# KUBODriver_DC.net
KiCad netlist of a schematic drawn in Altium Designer
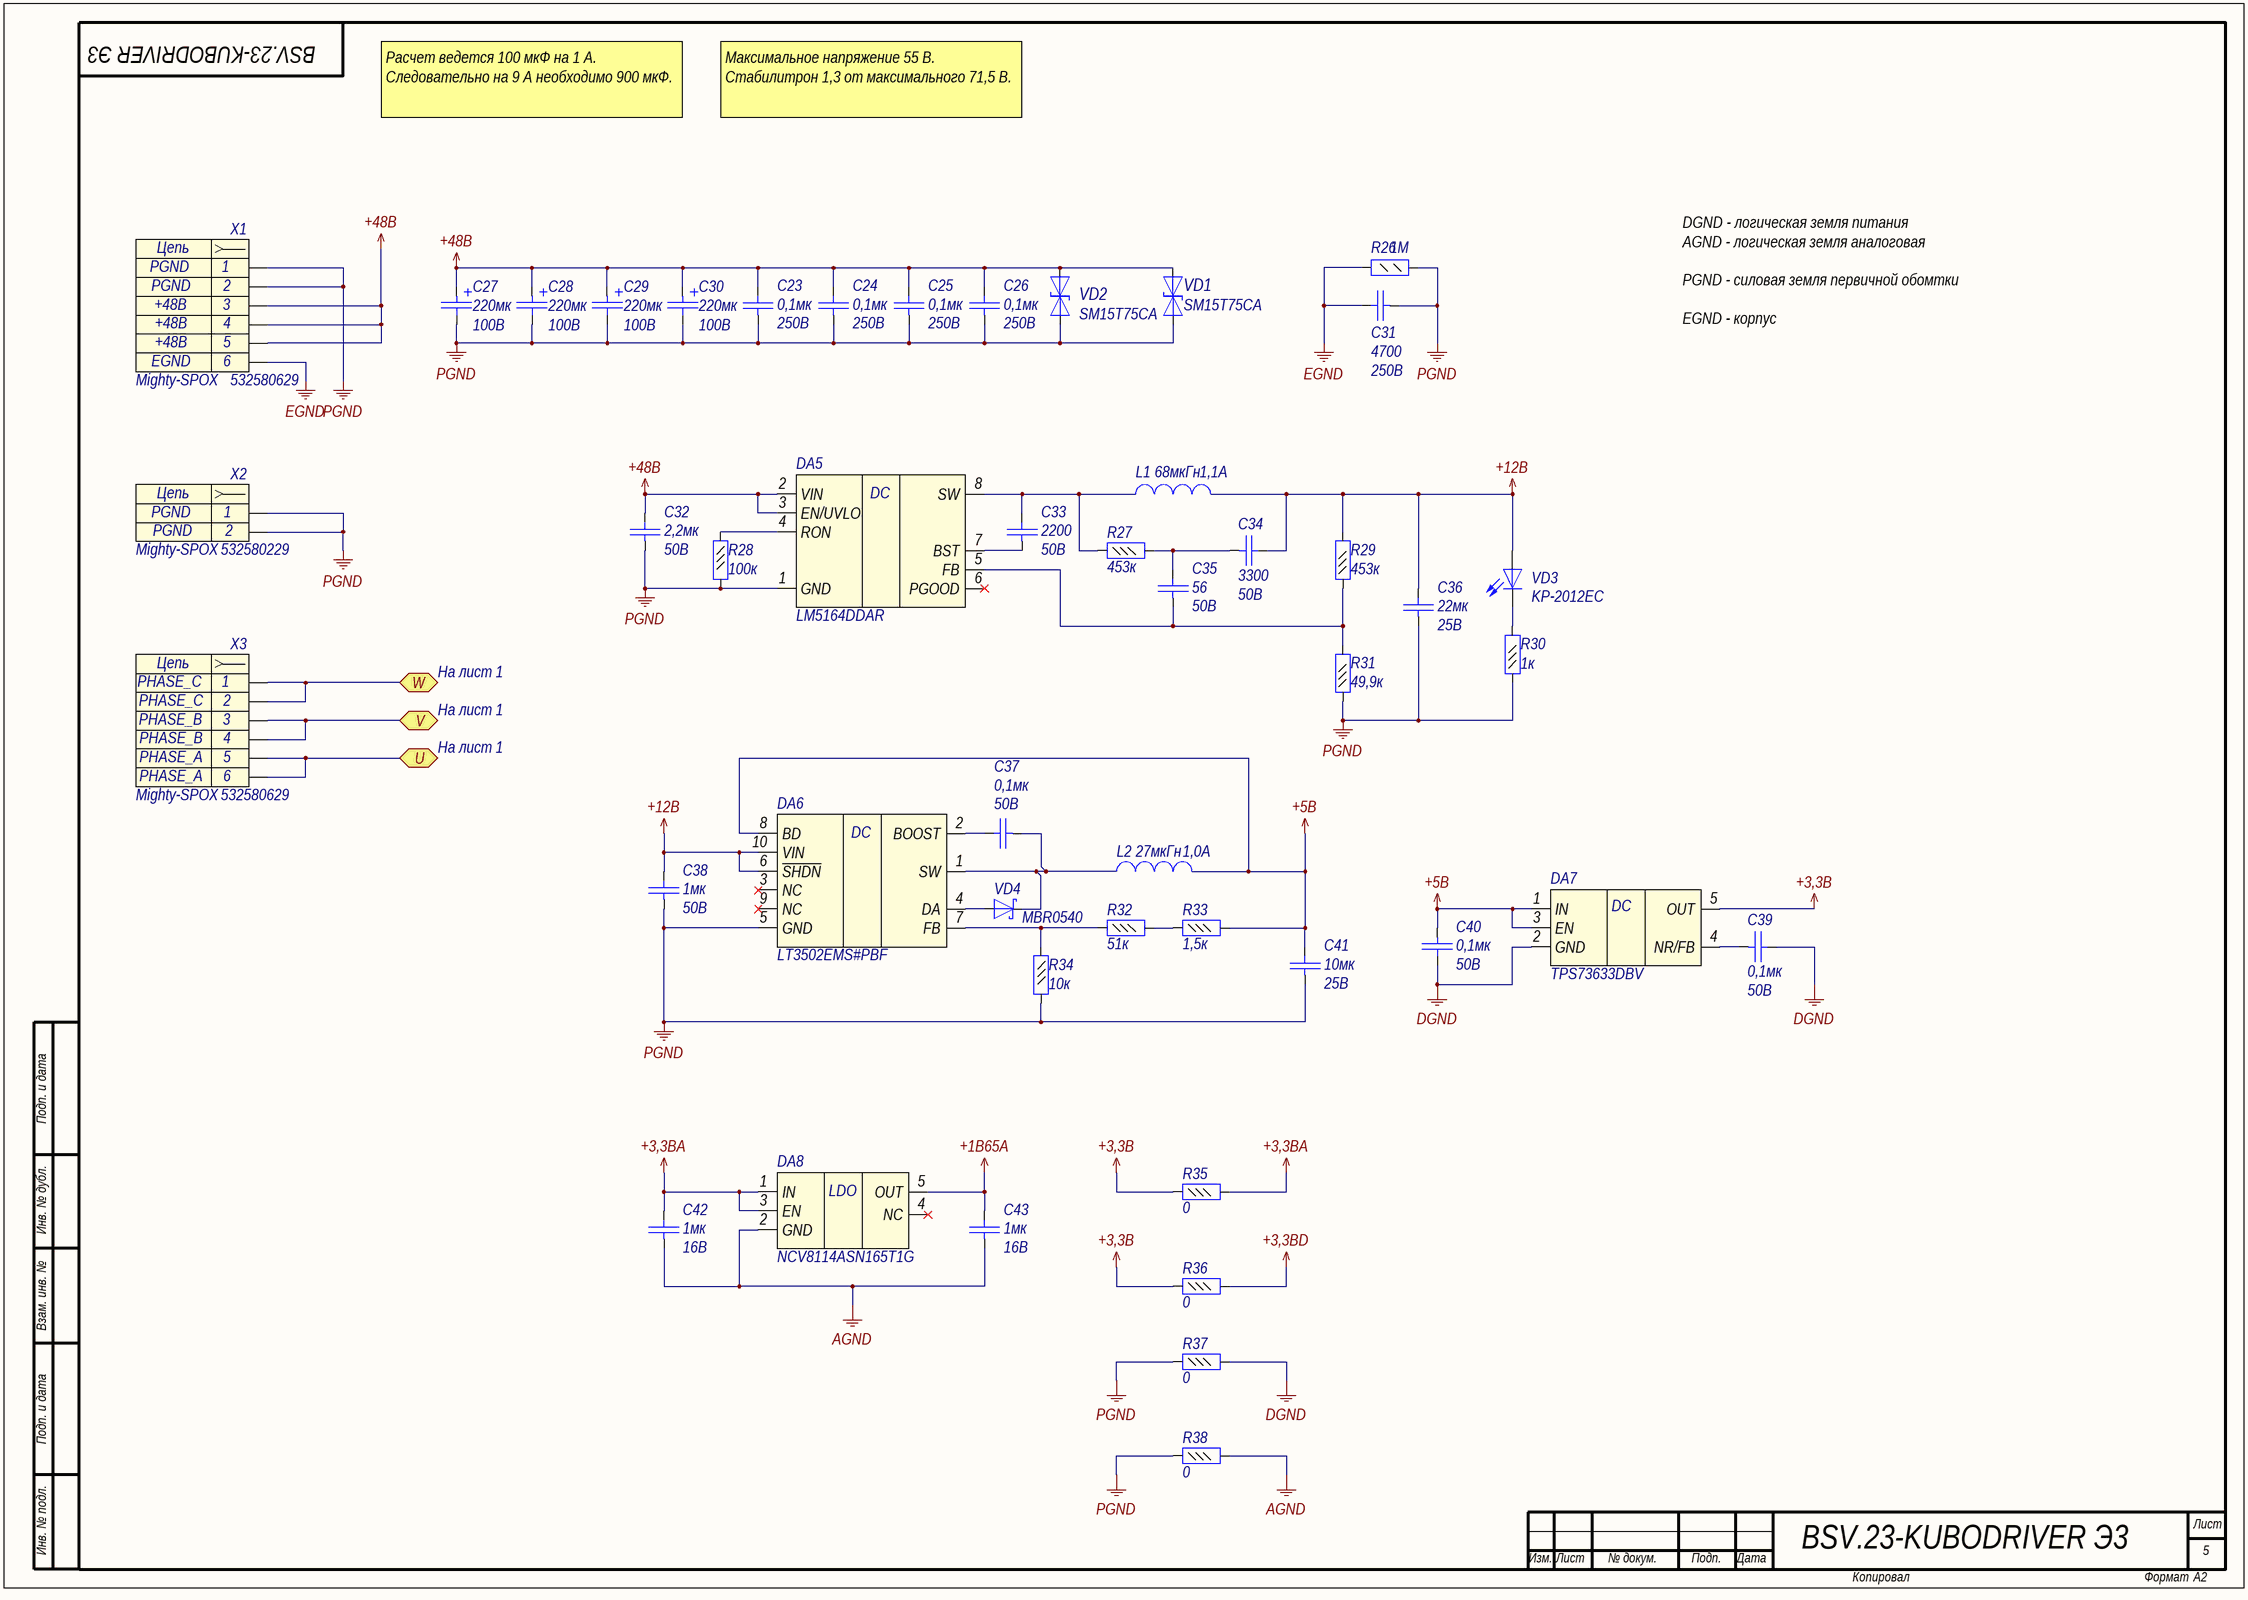
[diagram p0: KUBODriver_DC.SchDoc]

(export (version "E")
  (design (tool "Eeschema 10.0.6"))
  (components
    (comp (ref "C23")
      (value "0,1мк")
      (footprint "C1206")
      (description "Конденсатор")
      (fields
        (field (name "VOLTAGE") "250В")
        (field (name "PART NUMBER") "GRM31CR72E104K")
        (field (name "Comment") "Capacitor")
      )
      (libsource (lib "MOP44") (part "Capacitor"))
    )
    (comp (ref "C24")
      (value "0,1мк")
      (footprint "C1206")
      (description "Конденсатор")
      (fields
        (field (name "VOLTAGE") "250В")
        (field (name "PART NUMBER") "GRM31CR72E104K")
        (field (name "Comment") "Capacitor")
      )
      (libsource (lib "MOP44") (part "Capacitor"))
    )
    (comp (ref "C25")
      (value "0,1мк")
      (footprint "C1206")
      (description "Конденсатор")
      (fields
        (field (name "VOLTAGE") "250В")
        (field (name "PART NUMBER") "GRM31CR72E104K")
        (field (name "Comment") "Capacitor")
      )
      (libsource (lib "MOP44") (part "Capacitor"))
    )
    (comp (ref "C26")
      (value "0,1мк")
      (footprint "C1206")
      (description "Конденсатор")
      (fields
        (field (name "VOLTAGE") "250В")
        (field (name "PART NUMBER") "GRM31CR72E104K")
        (field (name "Comment") "Capacitor")
      )
      (libsource (lib "MOP44") (part "Capacitor"))
    )
    (comp (ref "C27")
      (value "220мк")
      (footprint "K50-35(12.5X25)_V")
      (description "Конденсатор полярный")
      (fields
        (field (name "VOLTAGE") "100B")
        (field (name "PART NUMBER") "B41851A9227M000")
        (field (name "Comment") "Capacitor_pol")
      )
      (libsource (lib "MOP44") (part "Capacitor_pol"))
    )
    (comp (ref "C28")
      (value "220мк")
      (footprint "K50-35(12.5X25)_V")
      (description "Конденсатор полярный")
      (fields
        (field (name "VOLTAGE") "100B")
        (field (name "PART NUMBER") "B41851A9227M000")
        (field (name "Comment") "Capacitor_pol")
      )
      (libsource (lib "MOP44") (part "Capacitor_pol"))
    )
    (comp (ref "C29")
      (value "220мк")
      (footprint "K50-35(12.5X25)_V")
      (description "Конденсатор полярный")
      (fields
        (field (name "VOLTAGE") "100B")
        (field (name "PART NUMBER") "B41851A9227M000")
        (field (name "Comment") "Capacitor_pol")
      )
      (libsource (lib "MOP44") (part "Capacitor_pol"))
    )
    (comp (ref "C30")
      (value "220мк")
      (footprint "K50-35(12.5X25)_V")
      (description "Конденсатор полярный")
      (fields
        (field (name "VOLTAGE") "100B")
        (field (name "PART NUMBER") "B41851A9227M000")
        (field (name "Comment") "Capacitor_pol")
      )
      (libsource (lib "MOP44") (part "Capacitor_pol"))
    )
    (comp (ref "C31")
      (value "4700")
      (footprint "C0805")
      (description "Конденсатор")
      (fields
        (field (name "VOLTAGE") "250В")
        (field (name "PART NUMBER") "GRM21AR72E472KW")
        (field (name "Comment") "Capacitor")
      )
      (libsource (lib "MOP44") (part "Capacitor"))
    )
    (comp (ref "C32")
      (value "2,2мк")
      (footprint "C0603")
      (description "Конденсатор")
      (fields
        (field (name "VOLTAGE") "50B")
        (field (name "PART NUMBER") "GRM188R71A225KE15D")
        (field (name "Comment") "Capacitor")
      )
      (libsource (lib "MOP44") (part "Capacitor"))
    )
    (comp (ref "C33")
      (value "2200")
      (footprint "C0402")
      (description "Конденсатор")
      (fields
        (field (name "VOLTAGE") "50B")
        (field (name "PART NUMBER") "GRM155R71H222K")
        (field (name "Comment") "Capacitor")
      )
      (libsource (lib "MOP44") (part "Capacitor"))
    )
    (comp (ref "C34")
      (value "3300")
      (footprint "C0402")
      (description "Конденсатор")
      (fields
        (field (name "VOLTAGE") "50В")
        (field (name "PART NUMBER") "GRM155R71H332KA01D ")
        (field (name "Comment") "Capacitor")
      )
      (libsource (lib "MOP44") (part "Capacitor"))
    )
    (comp (ref "C35")
      (value "56")
      (footprint "C0402")
      (description "Конденсатор")
      (fields
        (field (name "VOLTAGE") "50B")
        (field (name "PART NUMBER") "GRM1555C1H560J*")
        (field (name "Comment") "Capacitor")
      )
      (libsource (lib "MOP44") (part "Capacitor"))
    )
    (comp (ref "C36")
      (value "22мк")
      (footprint "C1210")
      (description "Конденсатор")
      (fields
        (field (name "VOLTAGE") "25B")
        (field (name "PART NUMBER") "TMK325B7226KMHT")
        (field (name "Comment") "Capacitor")
      )
      (libsource (lib "MOP44") (part "Capacitor"))
    )
    (comp (ref "C37")
      (value "0,1мк")
      (footprint "C0402")
      (description "Конденсатор")
      (fields
        (field (name "VOLTAGE") "50В")
        (field (name "PART NUMBER") "GRM155R71H104KE14D ")
        (field (name "Comment") "Capacitor")
      )
      (libsource (lib "MOP44") (part "Capacitor"))
    )
    (comp (ref "C38")
      (value "1мк")
      (footprint "C0805")
      (description "Конденсатор")
      (fields
        (field (name "VOLTAGE") "50B")
        (field (name "PART NUMBER") "GRM21BR71H105K")
        (field (name "Comment") "Capacitor")
      )
      (libsource (lib "MOP44") (part "Capacitor"))
    )
    (comp (ref "C39")
      (value "0,1мк")
      (footprint "C0402")
      (description "Конденсатор")
      (fields
        (field (name "VOLTAGE") "50В")
        (field (name "PART NUMBER") "GRM155R71H104KE14D ")
        (field (name "Comment") "Capacitor")
      )
      (libsource (lib "MOP44") (part "Capacitor"))
    )
    (comp (ref "C40")
      (value "0,1мк")
      (footprint "C0402")
      (description "Конденсатор")
      (fields
        (field (name "VOLTAGE") "50В")
        (field (name "PART NUMBER") "GRM155R71H104KE14D ")
        (field (name "Comment") "Capacitor")
      )
      (libsource (lib "MOP44") (part "Capacitor"))
    )
    (comp (ref "C41")
      (value "10мк")
      (footprint "C1206")
      (description "Конденсатор")
      (fields
        (field (name "VOLTAGE") "25В")
        (field (name "PART NUMBER") "GRM31CR71E106KA12L*")
        (field (name "Comment") "Capacitor")
      )
      (libsource (lib "MOP44") (part "Capacitor"))
    )
    (comp (ref "C42")
      (value "1мк")
      (footprint "C0603")
      (description "Конденсатор")
      (fields
        (field (name "VOLTAGE") "16B")
        (field (name "PART NUMBER") "GRM188R71C105KA12D**")
        (field (name "Comment") "Capacitor")
      )
      (libsource (lib "MOP44") (part "Capacitor"))
    )
    (comp (ref "C43")
      (value "1мк")
      (footprint "C0603")
      (description "Конденсатор")
      (fields
        (field (name "VOLTAGE") "16B")
        (field (name "PART NUMBER") "GRM188R71C105KA12D**")
        (field (name "Comment") "Capacitor")
      )
      (libsource (lib "MOP44") (part "Capacitor"))
    )
    (comp (ref "DA5")
      (value "LM5164")
      (footprint "SO Powerpad8")
      (description "1-A synchronous buck DC/DC converter with ultra-low IQ")
      (fields (field (name "PART NUMBER") "LM5164DDAR") (field (name "MANUFACTURER") "Texas Instruments"))
      (libsource (lib "MOP44") (part "LM5164"))
    )
    (comp (ref "DA6")
      (value "LT3502_MS")
      (footprint "MSOP10")
      (description "1.1MHz/2.2MHz, 500mA  Step-Down Regulators")
      (fields (field (name "PART NUMBER") "LT3502EMS#PBF") (field (name "MANUFACTURER") "Linear Technology"))
      (libsource (lib "MOP44") (part "LT3502_MS"))
    )
    (comp (ref "DA7")
      (value "TPS736DBV")
      (footprint "SOT23-5")
      (description "400-mA Low-Dropout Regulator with Reverse Current  Protection")
      (fields (field (name "PART NUMBER") "TPS73633DBV") (field (name "MANUFACTURER") "Texas Instruments"))
      (libsource (lib "MOP44") (part "TPS736DBV"))
    )
    (comp (ref "DA8")
      (value "NCV8114")
      (footprint "TSOP5")
      (description "300 mA CMOS Low Dropout  Regulator")
      (fields
        (field (name "PART NUMBER") "NCV8114ASN165T1G")
        (field (name "MANUFACTURER") "ON Semiconductor")
      )
      (libsource (lib "MOP44") (part "NCV8114"))
    )
    (comp (ref "L1")
      (value "68мкГн")
      (footprint "SDR1006")
      (description "EMI Suppression Filter")
      (fields
        (field (name "RATED CURRENT") "1,1A")
        (field (name "PART NUMBER") "SDR1006- 680KL")
        (field (name "Comment") "Inductor")
      )
      (libsource (lib "MOP44") (part "Inductor"))
    )
    (comp (ref "L2")
      (value "27мкГн")
      (footprint "SDR0604")
      (description "EMI Suppression Filter")
      (fields
        (field (name "RATED CURRENT") "1,0A")
        (field (name "PART NUMBER") "SDR0604- 270YL")
        (field (name "Comment") "Inductor")
      )
      (libsource (lib "MOP44") (part "Inductor"))
    )
    (comp (ref "R26")
      (value "1М")
      (footprint "R0805")
      (description "Резистор")
      (fields (field (name "PART NUMBER") "RC0805FR-071ML") (field (name "POWER") "0,125Вт"))
      (libsource (lib "MOP44") (part "Resistor_0,125Вт"))
    )
    (comp (ref "R27")
      (value "453к")
      (footprint "R0402")
      (description "Резистор")
      (fields (field (name "PART NUMBER") "RC0402FR-07453KL") (field (name "POWER") "0,062Вт"))
      (libsource (lib "MOP44") (part "Resistor_0,062Вт"))
    )
    (comp (ref "R28")
      (value "100к")
      (footprint "R0402")
      (description "Резистор")
      (fields (field (name "PART NUMBER") "RC0402FR-07100KL") (field (name "POWER") "0,062Вт"))
      (libsource (lib "") (part "Resistor_0,062Вт_1"))
    )
    (comp (ref "R29")
      (value "453к")
      (footprint "R0402")
      (description "Резистор")
      (fields (field (name "PART NUMBER") "RC0402FR-07453KL") (field (name "POWER") "0,062Вт"))
      (libsource (lib "") (part "Resistor_0,062Вт_2"))
    )
    (comp (ref "R30")
      (value "1к")
      (footprint "R0402")
      (description "Резистор")
      (fields (field (name "PART NUMBER") "RC0402FR-071KL") (field (name "POWER") "0,062Вт"))
      (libsource (lib "") (part "Resistor_0,062Вт_2"))
    )
    (comp (ref "R31")
      (value "49,9к")
      (footprint "R0402")
      (description "Резистор")
      (fields (field (name "PART NUMBER") "RC0402FR-0749K9L") (field (name "POWER") "0,062Вт"))
      (libsource (lib "") (part "Resistor_0,062Вт_2"))
    )
    (comp (ref "R32")
      (value "51к")
      (footprint "R0402")
      (description "Резистор")
      (fields (field (name "PART NUMBER") "RC0402FR-0751KL") (field (name "POWER") "0,062Вт"))
      (libsource (lib "MOP44") (part "Resistor_0,062Вт"))
    )
    (comp (ref "R33")
      (value "1,5к")
      (footprint "R0402")
      (description "Резистор")
      (fields (field (name "PART NUMBER") "RC0402FR-071K5") (field (name "POWER") "0,062Вт"))
      (libsource (lib "MOP44") (part "Resistor_0,062Вт"))
    )
    (comp (ref "R34")
      (value "10к")
      (footprint "R0402")
      (description "Резистор")
      (fields (field (name "PART NUMBER") "RC0402FR-0710KL") (field (name "POWER") "0,062Вт"))
      (libsource (lib "") (part "Resistor_0,062Вт_1"))
    )
    (comp (ref "R35")
      (value "0")
      (footprint "R0603")
      (description "Резистор")
      (fields (field (name "PART NUMBER") "RC0603FR-070RL") (field (name "POWER") "0,062Вт"))
      (libsource (lib "MOP44") (part "Resistor_0,062Вт"))
    )
    (comp (ref "R36")
      (value "0")
      (footprint "R0603")
      (description "Резистор")
      (fields (field (name "PART NUMBER") "RC0603FR-070RL") (field (name "POWER") "0,062Вт"))
      (libsource (lib "MOP44") (part "Resistor_0,062Вт"))
    )
    (comp (ref "R37")
      (value "0")
      (footprint "R0603")
      (description "Резистор")
      (fields (field (name "PART NUMBER") "RC0603FR-070RL") (field (name "POWER") "0,062Вт"))
      (libsource (lib "MOP44") (part "Resistor_0,062Вт"))
    )
    (comp (ref "R38")
      (value "0")
      (footprint "R0603")
      (description "Резистор")
      (fields (field (name "PART NUMBER") "RC0603FR-070RL") (field (name "POWER") "0,062Вт"))
      (libsource (lib "MOP44") (part "Resistor_0,062Вт"))
    )
    (comp (ref "VD1")
      (value "DiodeZenerDual")
      (footprint "SMC")
      (description "Cтабилитрон (диод выпрямительный лавинный) двусторонний")
      (fields (field (name "PART NUMBER") "SM15T75CA"))
      (libsource (lib "MOP44") (part "DiodeZenerDual"))
    )
    (comp (ref "VD2")
      (value "DiodeZenerDual")
      (footprint "SMC")
      (description "Cтабилитрон (диод выпрямительный лавинный) двусторонний")
      (fields (field (name "PART NUMBER") "SM15T75CA"))
      (libsource (lib "MOP44") (part "DiodeZenerDual"))
    )
    (comp (ref "VD3")
      (value "LED")
      (footprint "L_0805")
      (description "Светодиод")
      (fields (field (name "PART NUMBER") "KP-2012EC"))
      (libsource (lib "MOP44") (part "LED"))
    )
    (comp (ref "VD4")
      (value "DiodeSchottky")
      (footprint "SOD-123")
      (description "Диод Шоттки")
      (fields (field (name "PART NUMBER") "MBR0540"))
      (libsource (lib "MOP44") (part "DiodeSchottky"))
    )
    (comp (ref "X1")
      (value "Header_6_sct")
      (footprint "MOLEX_532580629")
      (description "Разъем - 6 конт. розетка")
      (fields (field (name "PART NAME") "Mighty-SPOX") (field (name "PART NUMBER") "532580629"))
      (libsource (lib "MOP44") (part "Header_6_sct"))
    )
    (comp (ref "X2")
      (value "Header_2_sct")
      (footprint "MOLEX_532580229")
      (description "Разъем - 2 конт. розетка")
      (fields (field (name "PART NAME") "Mighty-SPOX") (field (name "PART NUMBER") "532580229"))
      (libsource (lib "MOP44") (part "Header_2_sct"))
    )
    (comp (ref "X3")
      (value "Header_6_sct")
      (footprint "MOLEX_532580629")
      (description "Разъем - 6 конт. розетка")
      (fields (field (name "PART NAME") "Mighty-SPOX") (field (name "PART NUMBER") "532580629"))
      (libsource (lib "MOP44") (part "Header_6_sct"))
    )
  )
  (nets
    (net (code "1") (name "+1B65A") (class "Default")
      (node (ref "C43") (pin "2") (pinfunction "2_2") (pintype "passive"))
      (node (ref "DA8") (pin "5") (pinfunction "OUT_5") (pintype "power_in"))
    )
    (net (code "2") (name "+3,3B") (class "Default")
      (node (ref "DA7") (pin "5") (pinfunction "OUT_5") (pintype "power_in"))
      (node (ref "R35") (pin "1") (pinfunction "1_1") (pintype "passive"))
      (node (ref "R36") (pin "1") (pinfunction "1_1") (pintype "passive"))
    )
    (net (code "3") (name "+3,3BA") (class "Default")
      (node (ref "C42") (pin "2") (pinfunction "2_2") (pintype "passive"))
      (node (ref "DA8") (pin "1") (pinfunction "IN_1") (pintype "power_in"))
      (node (ref "DA8") (pin "3") (pinfunction "EN_3") (pintype "power_in"))
      (node (ref "R35") (pin "2") (pinfunction "2_2") (pintype "passive"))
    )
    (net (code "4") (name "+3,3BD") (class "Default")
      (node (ref "R36") (pin "2") (pinfunction "2_2") (pintype "passive"))
    )
    (net (code "5") (name "+5B") (class "Default")
      (node (ref "C40") (pin "1") (pinfunction "1_1") (pintype "passive"))
      (node (ref "C41") (pin "2") (pinfunction "2_2") (pintype "passive"))
      (node (ref "DA6") (pin "8") (pinfunction "BD_8") (pintype "power_in"))
      (node (ref "DA7") (pin "1") (pinfunction "IN_1") (pintype "power_in"))
      (node (ref "DA7") (pin "3") (pinfunction "EN_3") (pintype "power_in"))
      (node (ref "L2") (pin "2") (pinfunction "2_2") (pintype "passive"))
      (node (ref "R33") (pin "2") (pinfunction "2_2") (pintype "passive"))
    )
    (net (code "6") (name "+12B") (class "Default")
      (node (ref "C34") (pin "2") (pinfunction "2_2") (pintype "passive"))
      (node (ref "C36") (pin "2") (pinfunction "2_2") (pintype "passive"))
      (node (ref "C38") (pin "2") (pinfunction "2_2") (pintype "passive"))
      (node (ref "DA6") (pin "10") (pinfunction "VIN_10") (pintype "power_in"))
      (node (ref "DA6") (pin "6") (pinfunction "~{SHDN}_6") (pintype "power_in"))
      (node (ref "L1") (pin "2") (pinfunction "2_2") (pintype "passive"))
      (node (ref "R29") (pin "2") (pinfunction "2_2") (pintype "passive"))
      (node (ref "VD3") (pin "2") (pinfunction "A_2") (pintype "passive"))
    )
    (net (code "7") (name "+48B") (class "Default")
      (node (ref "C23") (pin "2") (pinfunction "2_2") (pintype "passive"))
      (node (ref "C24") (pin "2") (pinfunction "2_2") (pintype "passive"))
      (node (ref "C25") (pin "2") (pinfunction "2_2") (pintype "passive"))
      (node (ref "C26") (pin "2") (pinfunction "2_2") (pintype "passive"))
      (node (ref "C27") (pin "1") (pinfunction "1_1") (pintype "passive"))
      (node (ref "C28") (pin "1") (pinfunction "1_1") (pintype "passive"))
      (node (ref "C29") (pin "1") (pinfunction "1_1") (pintype "passive"))
      (node (ref "C30") (pin "1") (pinfunction "1_1") (pintype "passive"))
      (node (ref "C32") (pin "2") (pinfunction "2_2") (pintype "passive"))
      (node (ref "DA5") (pin "2") (pinfunction "VIN_2") (pintype "power_in"))
      (node (ref "DA5") (pin "3") (pinfunction "EN/UVLO_3") (pintype "power_in"))
      (node (ref "VD1") (pin "1") (pinfunction "K_1") (pintype "passive"))
      (node (ref "VD2") (pin "2") (pinfunction "A_2") (pintype "passive"))
      (node (ref "X1") (pin "3") (pinfunction "3_3") (pintype "passive"))
      (node (ref "X1") (pin "4") (pinfunction "4_4") (pintype "passive"))
      (node (ref "X1") (pin "5") (pinfunction "5_5") (pintype "passive"))
    )
    (net (code "8") (name "/U") (class "Default")
      (node (ref "X3") (pin "5") (pinfunction "5_5") (pintype "passive"))
      (node (ref "X3") (pin "6") (pinfunction "6_6") (pintype "passive"))
    )
    (net (code "9") (name "/V") (class "Default")
      (node (ref "X3") (pin "3") (pinfunction "3_3") (pintype "passive"))
      (node (ref "X3") (pin "4") (pinfunction "4_4") (pintype "passive"))
    )
    (net (code "10") (name "/W") (class "Default")
      (node (ref "X3") (pin "1") (pinfunction "1_1") (pintype "passive"))
      (node (ref "X3") (pin "2") (pinfunction "2_2") (pintype "passive"))
    )
    (net (code "11") (name "AGND") (class "Default")
      (node (ref "C42") (pin "1") (pinfunction "1_1") (pintype "passive"))
      (node (ref "C43") (pin "1") (pinfunction "1_1") (pintype "passive"))
      (node (ref "DA8") (pin "2") (pinfunction "GND_2") (pintype "power_in"))
      (node (ref "R38") (pin "2") (pinfunction "2_2") (pintype "passive"))
    )
    (net (code "12") (name "DGND") (class "Default")
      (node (ref "C39") (pin "2") (pinfunction "2_2") (pintype "passive"))
      (node (ref "C40") (pin "2") (pinfunction "2_2") (pintype "passive"))
      (node (ref "DA7") (pin "2") (pinfunction "GND_2") (pintype "power_in"))
      (node (ref "R37") (pin "2") (pinfunction "2_2") (pintype "passive"))
    )
    (net (code "13") (name "EGND") (class "Default")
      (node (ref "C31") (pin "2") (pinfunction "2_2") (pintype "passive"))
      (node (ref "R26") (pin "2") (pinfunction "2_2") (pintype "passive"))
      (node (ref "X1") (pin "6") (pinfunction "6_6") (pintype "passive"))
    )
    (net (code "14") (name "Net-(C34-Pad1)") (class "Default")
      (node (ref "C34") (pin "1") (pinfunction "1_1") (pintype "passive"))
      (node (ref "C35") (pin "2") (pinfunction "2_2") (pintype "passive"))
      (node (ref "R27") (pin "2") (pinfunction "2_2") (pintype "passive"))
    )
    (net (code "15") (name "Net-(DA5-BST)") (class "Default")
      (node (ref "C33") (pin "1") (pinfunction "1_1") (pintype "passive"))
      (node (ref "DA5") (pin "7") (pinfunction "BST_7") (pintype "power_in"))
    )
    (net (code "16") (name "Net-(DA5-FB)") (class "Default")
      (node (ref "C35") (pin "1") (pinfunction "1_1") (pintype "passive"))
      (node (ref "DA5") (pin "5") (pinfunction "FB_5") (pintype "power_in"))
      (node (ref "R29") (pin "1") (pinfunction "1_1") (pintype "passive"))
      (node (ref "R31") (pin "2") (pinfunction "2_2") (pintype "passive"))
    )
    (net (code "17") (name "Net-(DA5-RON)") (class "Default")
      (node (ref "DA5") (pin "4") (pinfunction "RON_4") (pintype "power_in"))
      (node (ref "R28") (pin "1") (pinfunction "1_1") (pintype "passive"))
    )
    (net (code "18") (name "Net-(DA5-SW)") (class "Default")
      (node (ref "C33") (pin "2") (pinfunction "2_2") (pintype "passive"))
      (node (ref "DA5") (pin "8") (pinfunction "SW_8") (pintype "power_in"))
      (node (ref "L1") (pin "1") (pinfunction "1_1") (pintype "passive"))
      (node (ref "R27") (pin "1") (pinfunction "1_1") (pintype "passive"))
    )
    (net (code "19") (name "Net-(DA6-BOOST)") (class "Default")
      (node (ref "C37") (pin "2") (pinfunction "2_2") (pintype "passive"))
      (node (ref "DA6") (pin "2") (pinfunction "BOOST_2") (pintype "power_in"))
    )
    (net (code "20") (name "Net-(DA6-DA)") (class "Default")
      (node (ref "DA6") (pin "4") (pinfunction "DA_4") (pintype "power_in"))
      (node (ref "VD4") (pin "2") (pinfunction "A_2") (pintype "passive"))
    )
    (net (code "21") (name "Net-(DA6-FB)") (class "Default")
      (node (ref "DA6") (pin "7") (pinfunction "FB_7") (pintype "power_in"))
      (node (ref "R32") (pin "1") (pinfunction "1_1") (pintype "passive"))
      (node (ref "R34") (pin "1") (pinfunction "1_1") (pintype "passive"))
    )
    (net (code "22") (name "Net-(DA6-SW)") (class "Default")
      (node (ref "C37") (pin "1") (pinfunction "1_1") (pintype "passive"))
      (node (ref "DA6") (pin "1") (pinfunction "SW_1") (pintype "power_in"))
      (node (ref "L2") (pin "1") (pinfunction "1_1") (pintype "passive"))
      (node (ref "VD4") (pin "1") (pinfunction "K_1") (pintype "passive"))
    )
    (net (code "23") (name "Net-(DA7-NR{slash}FB)") (class "Default")
      (node (ref "C39") (pin "1") (pinfunction "1_1") (pintype "passive"))
      (node (ref "DA7") (pin "4") (pinfunction "NR/FB_4") (pintype "power_in"))
    )
    (net (code "24") (name "Net-(R32-Pad2)") (class "Default")
      (node (ref "R32") (pin "2") (pinfunction "2_2") (pintype "passive"))
      (node (ref "R33") (pin "1") (pinfunction "1_1") (pintype "passive"))
    )
    (net (code "25") (name "Net-(VD3-K)") (class "Default")
      (node (ref "R30") (pin "2") (pinfunction "2_2") (pintype "passive"))
      (node (ref "VD3") (pin "1") (pinfunction "K_1") (pintype "passive"))
    )
    (net (code "26") (name "PGND") (class "Default")
      (node (ref "C23") (pin "1") (pinfunction "1_1") (pintype "passive"))
      (node (ref "C24") (pin "1") (pinfunction "1_1") (pintype "passive"))
      (node (ref "C25") (pin "1") (pinfunction "1_1") (pintype "passive"))
      (node (ref "C26") (pin "1") (pinfunction "1_1") (pintype "passive"))
      (node (ref "C27") (pin "2") (pinfunction "2_2") (pintype "passive"))
      (node (ref "C28") (pin "2") (pinfunction "2_2") (pintype "passive"))
      (node (ref "C29") (pin "2") (pinfunction "2_2") (pintype "passive"))
      (node (ref "C30") (pin "2") (pinfunction "2_2") (pintype "passive"))
      (node (ref "C31") (pin "1") (pinfunction "1_1") (pintype "passive"))
      (node (ref "C32") (pin "1") (pinfunction "1_1") (pintype "passive"))
      (node (ref "C36") (pin "1") (pinfunction "1_1") (pintype "passive"))
      (node (ref "C38") (pin "1") (pinfunction "1_1") (pintype "passive"))
      (node (ref "C41") (pin "1") (pinfunction "1_1") (pintype "passive"))
      (node (ref "DA5") (pin "1") (pinfunction "GND_1") (pintype "power_in"))
      (node (ref "DA6") (pin "5") (pinfunction "GND_5") (pintype "power_in"))
      (node (ref "R26") (pin "1") (pinfunction "1_1") (pintype "passive"))
      (node (ref "R28") (pin "2") (pinfunction "2_2") (pintype "passive"))
      (node (ref "R30") (pin "1") (pinfunction "1_1") (pintype "passive"))
      (node (ref "R31") (pin "1") (pinfunction "1_1") (pintype "passive"))
      (node (ref "R34") (pin "2") (pinfunction "2_2") (pintype "passive"))
      (node (ref "R37") (pin "1") (pinfunction "1_1") (pintype "passive"))
      (node (ref "R38") (pin "1") (pinfunction "1_1") (pintype "passive"))
      (node (ref "VD1") (pin "2") (pinfunction "A_2") (pintype "passive"))
      (node (ref "VD2") (pin "1") (pinfunction "K_1") (pintype "passive"))
      (node (ref "X1") (pin "1") (pinfunction "1_1") (pintype "passive"))
      (node (ref "X1") (pin "2") (pinfunction "2_2") (pintype "passive"))
      (node (ref "X2") (pin "1") (pinfunction "1_1") (pintype "passive"))
      (node (ref "X2") (pin "2") (pinfunction "2_2") (pintype "passive"))
    )
    (net (code "27") (name "unconnected-(DA5-PGOOD-Pad6)") (class "Default")
      (node (ref "DA5") (pin "6") (pinfunction "PGOOD_6") (pintype "power_in+no_connect"))
    )
    (net (code "28") (name "unconnected-(DA6-NC-Pad3)") (class "Default")
      (node (ref "DA6") (pin "3") (pinfunction "NC_3") (pintype "power_in+no_connect"))
    )
    (net (code "29") (name "unconnected-(DA6-NC-Pad9)") (class "Default")
      (node (ref "DA6") (pin "9") (pinfunction "NC_9") (pintype "power_in+no_connect"))
    )
    (net (code "30") (name "unconnected-(DA8-NC-Pad4)") (class "Default")
      (node (ref "DA8") (pin "4") (pinfunction "NC_4") (pintype "power_in+no_connect"))
    )
  )
)
